# Pinduinov3-Nano-WPC-TPL521-AR.net
KiCad netlist of a schematic drawn in EAGLE
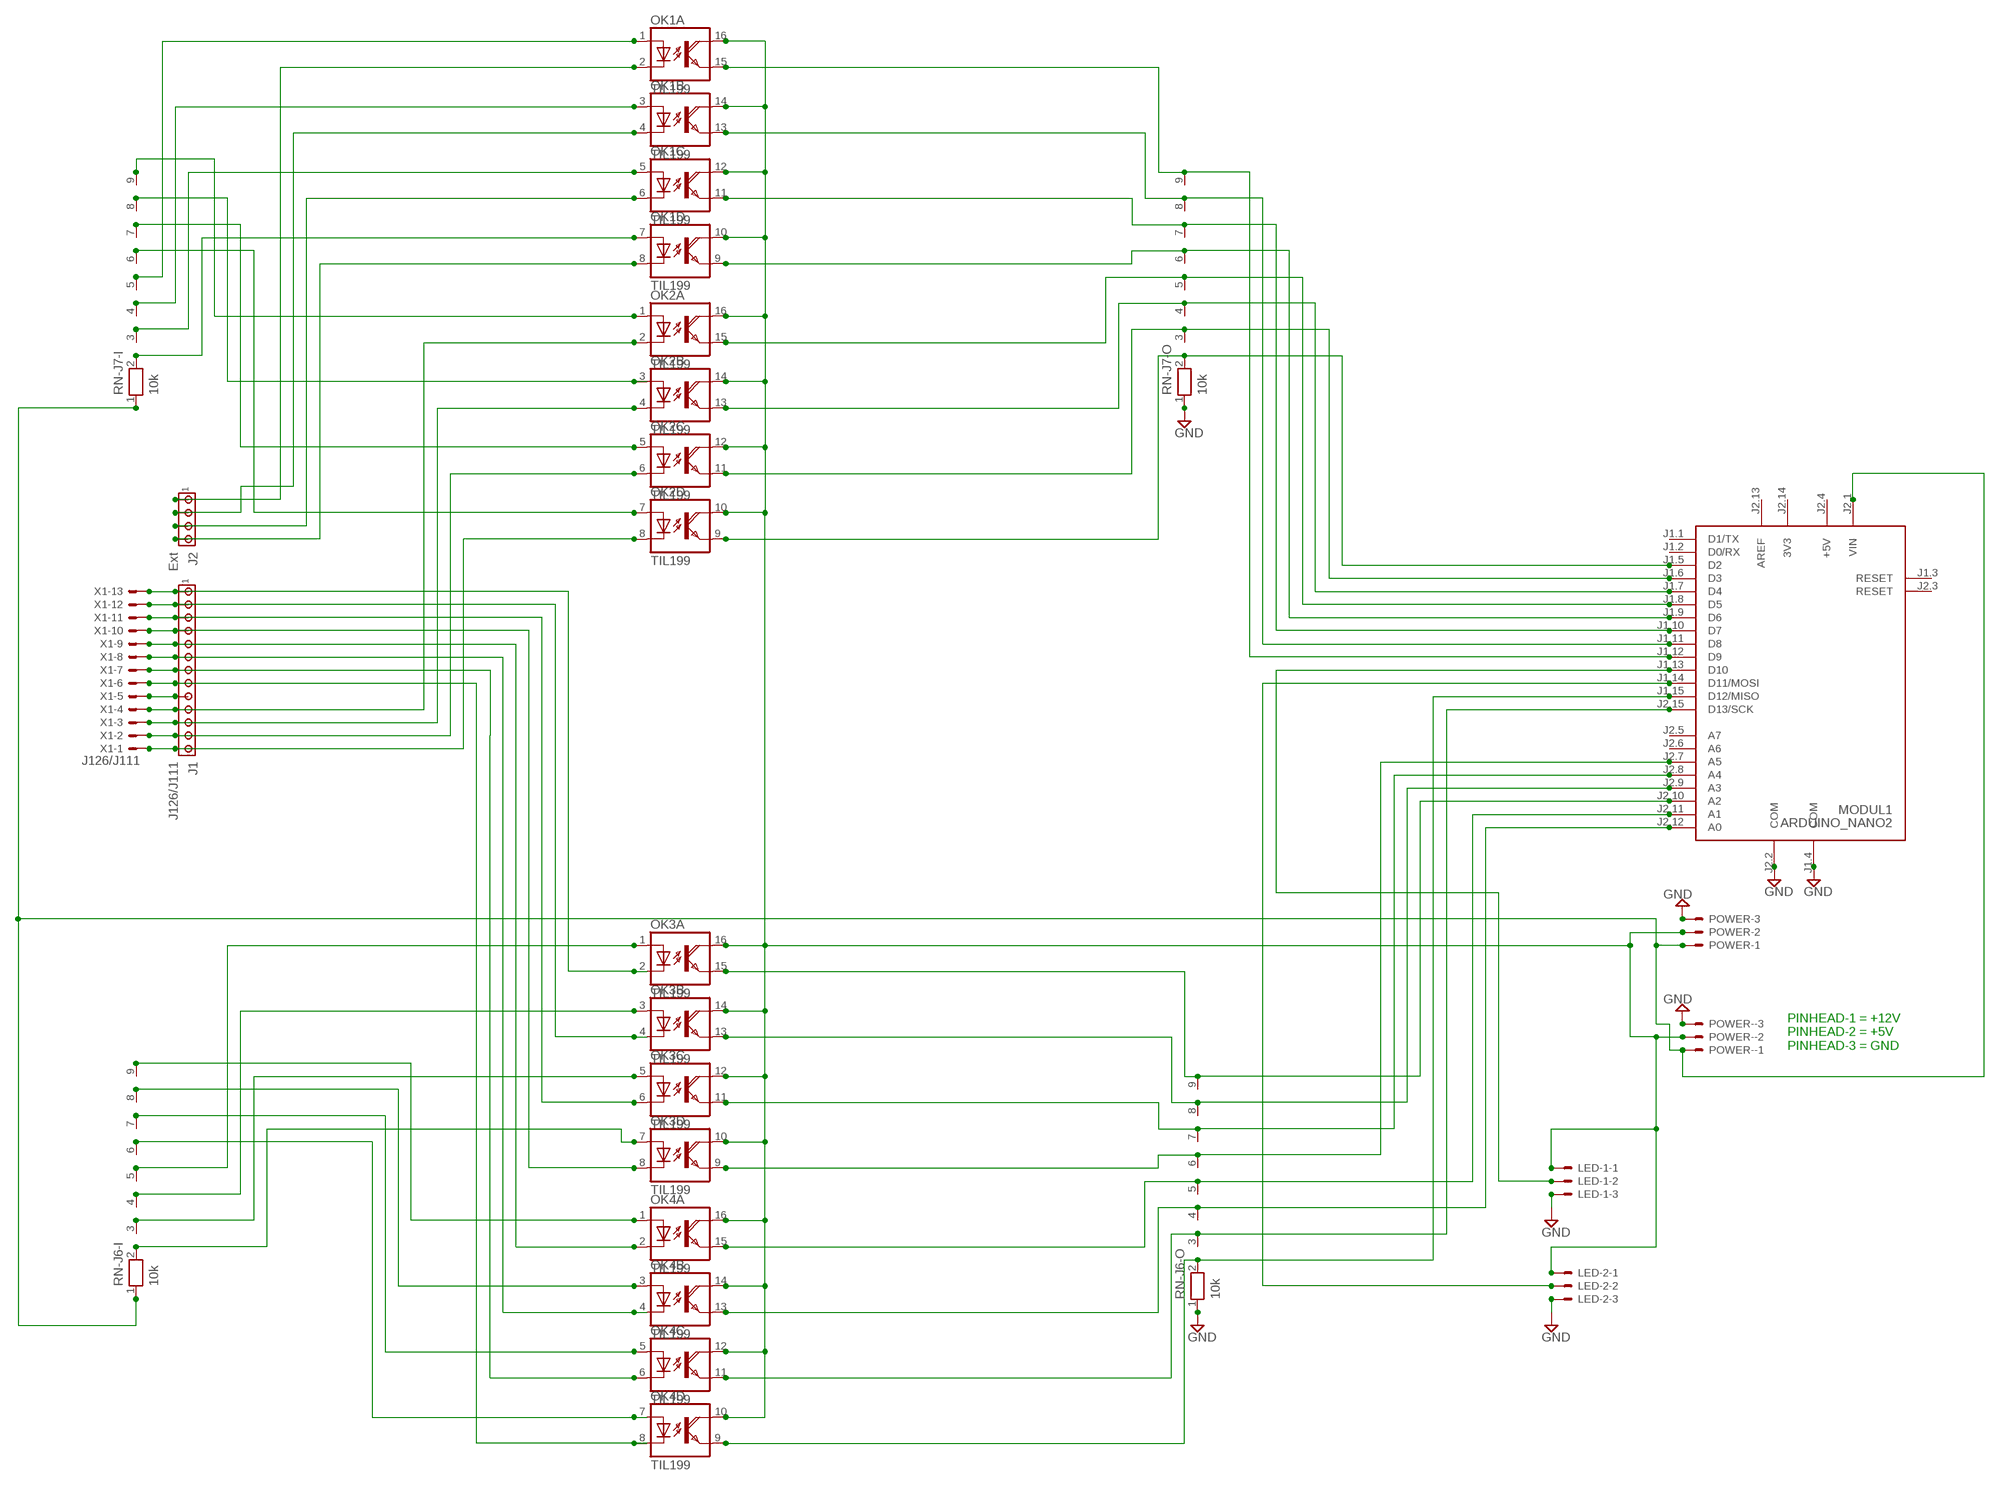
[diagram p0: schematic, sheet 1]

(export (version "E")
  (design (tool "Eeschema 10.0.6"))
  (components
    (comp (ref "J1")
      (value "J126/J111")
      (footprint "eagle-import:1X13MTA")
      (libsource (lib "eagle-import") (part "MTA13-156"))
    )
    (comp (ref "J2")
      (value "Ext")
      (footprint "eagle-import:1X4MTA")
      (libsource (lib "eagle-import") (part "MTA04-156"))
    )
    (comp (ref "LED-1")
      (value "22-23-2031")
      (footprint "eagle-import:22-23-2031")
      (fields (field (name "MF") "MOLEX"))
      (libsource (lib "eagle-import") (part "22-23-2031"))
    )
    (comp (ref "LED-2")
      (value "22-23-2031")
      (footprint "eagle-import:22-23-2031")
      (fields (field (name "MF") "MOLEX"))
      (libsource (lib "eagle-import") (part "22-23-2031"))
    )
    (comp (ref "MODUL1")
      (value "ARDUINO_NANO2")
      (footprint "eagle-import:ARDUINO_NANO2")
      (libsource (lib "eagle-import") (part "ARDUINO_NANO2"))
    )
    (comp (ref "OK1")
      (value "TIL199")
      (footprint "eagle-import:DIL16")
      (fields (field (name "MPN") "TIL 199"))
      (libsource (lib "eagle-import") (part "TIL199"))
    )
    (comp (ref "OK2")
      (value "TIL199")
      (footprint "eagle-import:DIL16")
      (fields (field (name "MPN") "TIL 199"))
      (libsource (lib "eagle-import") (part "TIL199"))
    )
    (comp (ref "OK3")
      (value "TIL199")
      (footprint "eagle-import:DIL16")
      (fields (field (name "MPN") "TIL 199"))
      (libsource (lib "eagle-import") (part "TIL199"))
    )
    (comp (ref "OK4")
      (value "TIL199")
      (footprint "eagle-import:DIL16")
      (fields (field (name "MPN") "TIL 199"))
      (libsource (lib "eagle-import") (part "TIL199"))
    )
    (comp (ref "POWER")
      (value "22-23-2031")
      (footprint "eagle-import:22-23-2031")
      (fields (field (name "MF") "MOLEX"))
      (libsource (lib "eagle-import") (part "22-23-2031"))
    )
    (comp (ref "POWER-")
      (value "22-23-2031")
      (footprint "eagle-import:22-23-2031")
      (fields (field (name "MF") "MOLEX"))
      (libsource (lib "eagle-import") (part "22-23-2031"))
    )
    (comp (ref "RN-J6-I")
      (value "10k")
      (footprint "eagle-import:RN-9")
      (libsource (lib "eagle-import") (part "RN08"))
    )
    (comp (ref "RN-J6-O")
      (value "10k")
      (footprint "eagle-import:RN-9")
      (libsource (lib "eagle-import") (part "RN08"))
    )
    (comp (ref "RN-J7-I")
      (value "10k")
      (footprint "eagle-import:RN-9")
      (libsource (lib "eagle-import") (part "RN08"))
    )
    (comp (ref "RN-J7-O")
      (value "10k")
      (footprint "eagle-import:RN-9")
      (libsource (lib "eagle-import") (part "RN08"))
    )
    (comp (ref "X1")
      (value "J126/J111")
      (footprint "eagle-import:KK-156-13")
      (libsource (lib "eagle-import") (part "KK-156-13"))
    )
  )
  (nets
    (net (code "1") (name "/+5V") (class "Default")
      (node (ref "MODUL1") (pin "J2.4") (pinfunction "+5V_J2.4") (pintype "power_in"))
    )
    (net (code "2") (name "/3V3") (class "Default")
      (node (ref "MODUL1") (pin "J2.14") (pinfunction "3V3_J2.14") (pintype "power_in"))
    )
    (net (code "3") (name "/AREF") (class "Default")
      (node (ref "MODUL1") (pin "J2.13") (pinfunction "AREF_J2.13") (pintype "power_in"))
    )
    (net (code "4") (name "GND") (class "Default")
      (node (ref "LED-1") (pin "3") (pinfunction "S_3") (pintype "passive"))
      (node (ref "LED-2") (pin "3") (pinfunction "S_3") (pintype "passive"))
      (node (ref "MODUL1") (pin "J1.4") (pinfunction "COM_J1.4") (pintype "power_in"))
      (node (ref "MODUL1") (pin "J2.2") (pinfunction "COM_J2.2") (pintype "power_in"))
      (node (ref "POWER") (pin "3") (pinfunction "S_3") (pintype "passive"))
      (node (ref "POWER-") (pin "3") (pinfunction "S_3") (pintype "passive"))
      (node (ref "RN-J6-O") (pin "1") (pinfunction "1_1") (pintype "passive"))
      (node (ref "RN-J7-O") (pin "1") (pinfunction "1_1") (pintype "passive"))
    )
    (net (code "5") (name "Net-(LED-1A-S)") (class "Default")
      (node (ref "LED-1") (pin "1") (pinfunction "S_1") (pintype "passive"))
      (node (ref "LED-2") (pin "1") (pinfunction "S_1") (pintype "passive"))
      (node (ref "OK1") (pin "10") (pinfunction "COL_10") (pintype "passive"))
      (node (ref "OK1") (pin "12") (pinfunction "COL_12") (pintype "passive"))
      (node (ref "OK1") (pin "14") (pinfunction "COL_14") (pintype "passive"))
      (node (ref "OK1") (pin "16") (pinfunction "COL_16") (pintype "passive"))
      (node (ref "OK2") (pin "10") (pinfunction "COL_10") (pintype "passive"))
      (node (ref "OK2") (pin "12") (pinfunction "COL_12") (pintype "passive"))
      (node (ref "OK2") (pin "14") (pinfunction "COL_14") (pintype "passive"))
      (node (ref "OK2") (pin "16") (pinfunction "COL_16") (pintype "passive"))
      (node (ref "OK3") (pin "10") (pinfunction "COL_10") (pintype "passive"))
      (node (ref "OK3") (pin "12") (pinfunction "COL_12") (pintype "passive"))
      (node (ref "OK3") (pin "14") (pinfunction "COL_14") (pintype "passive"))
      (node (ref "OK3") (pin "16") (pinfunction "COL_16") (pintype "passive"))
      (node (ref "OK4") (pin "10") (pinfunction "COL_10") (pintype "passive"))
      (node (ref "OK4") (pin "12") (pinfunction "COL_12") (pintype "passive"))
      (node (ref "OK4") (pin "14") (pinfunction "COL_14") (pintype "passive"))
      (node (ref "OK4") (pin "16") (pinfunction "COL_16") (pintype "passive"))
      (node (ref "POWER") (pin "2") (pinfunction "S_2") (pintype "passive"))
      (node (ref "POWER-") (pin "2") (pinfunction "S_2") (pintype "passive"))
    )
    (net (code "6") (name "Net-(LED-1B-S)") (class "Default")
      (node (ref "LED-1") (pin "2") (pinfunction "S_2") (pintype "passive"))
      (node (ref "MODUL1") (pin "J1.13") (pinfunction "D10_J1.13") (pintype "bidirectional"))
    )
    (net (code "7") (name "Net-(LED-2B-S)") (class "Default")
      (node (ref "LED-2") (pin "2") (pinfunction "S_2") (pintype "passive"))
      (node (ref "MODUL1") (pin "J1.14") (pinfunction "D11/MOSI_J1.14") (pintype "bidirectional"))
    )
    (net (code "8") (name "Net-(MODUL1-A0)") (class "Default")
      (node (ref "MODUL1") (pin "J2.12") (pinfunction "A0_J2.12") (pintype "bidirectional"))
      (node (ref "OK4") (pin "13") (pinfunction "EMI_13") (pintype "passive"))
      (node (ref "RN-J6-O") (pin "4") (pinfunction "4_4") (pintype "passive"))
    )
    (net (code "9") (name "Net-(MODUL1-A1)") (class "Default")
      (node (ref "MODUL1") (pin "J2.11") (pinfunction "A1_J2.11") (pintype "bidirectional"))
      (node (ref "OK4") (pin "15") (pinfunction "EMI_15") (pintype "passive"))
      (node (ref "RN-J6-O") (pin "5") (pinfunction "5_5") (pintype "passive"))
    )
    (net (code "10") (name "Net-(MODUL1-A2)") (class "Default")
      (node (ref "MODUL1") (pin "J2.10") (pinfunction "A2_J2.10") (pintype "bidirectional"))
      (node (ref "OK3") (pin "15") (pinfunction "EMI_15") (pintype "passive"))
      (node (ref "RN-J6-O") (pin "9") (pinfunction "9_9") (pintype "passive"))
    )
    (net (code "11") (name "Net-(MODUL1-A3)") (class "Default")
      (node (ref "MODUL1") (pin "J2.9") (pinfunction "A3_J2.9") (pintype "bidirectional"))
      (node (ref "OK3") (pin "13") (pinfunction "EMI_13") (pintype "passive"))
      (node (ref "RN-J6-O") (pin "8") (pinfunction "8_8") (pintype "passive"))
    )
    (net (code "12") (name "Net-(MODUL1-A4)") (class "Default")
      (node (ref "MODUL1") (pin "J2.8") (pinfunction "A4_J2.8") (pintype "bidirectional"))
      (node (ref "OK3") (pin "11") (pinfunction "EMI_11") (pintype "passive"))
      (node (ref "RN-J6-O") (pin "7") (pinfunction "7_7") (pintype "passive"))
    )
    (net (code "13") (name "Net-(MODUL1-A5)") (class "Default")
      (node (ref "MODUL1") (pin "J2.7") (pinfunction "A5_J2.7") (pintype "bidirectional"))
      (node (ref "OK3") (pin "9") (pinfunction "EMI_9") (pintype "passive"))
      (node (ref "RN-J6-O") (pin "6") (pinfunction "6_6") (pintype "passive"))
    )
    (net (code "14") (name "Net-(MODUL1-D2)") (class "Default")
      (node (ref "MODUL1") (pin "J1.5") (pinfunction "D2_J1.5") (pintype "bidirectional"))
      (node (ref "OK2") (pin "9") (pinfunction "EMI_9") (pintype "passive"))
      (node (ref "RN-J7-O") (pin "2") (pinfunction "2_2") (pintype "passive"))
    )
    (net (code "15") (name "Net-(MODUL1-D3)") (class "Default")
      (node (ref "MODUL1") (pin "J1.6") (pinfunction "D3_J1.6") (pintype "bidirectional"))
      (node (ref "OK2") (pin "11") (pinfunction "EMI_11") (pintype "passive"))
      (node (ref "RN-J7-O") (pin "3") (pinfunction "3_3") (pintype "passive"))
    )
    (net (code "16") (name "Net-(MODUL1-D4)") (class "Default")
      (node (ref "MODUL1") (pin "J1.7") (pinfunction "D4_J1.7") (pintype "bidirectional"))
      (node (ref "OK2") (pin "13") (pinfunction "EMI_13") (pintype "passive"))
      (node (ref "RN-J7-O") (pin "4") (pinfunction "4_4") (pintype "passive"))
    )
    (net (code "17") (name "Net-(MODUL1-D5)") (class "Default")
      (node (ref "MODUL1") (pin "J1.8") (pinfunction "D5_J1.8") (pintype "bidirectional"))
      (node (ref "OK2") (pin "15") (pinfunction "EMI_15") (pintype "passive"))
      (node (ref "RN-J7-O") (pin "5") (pinfunction "5_5") (pintype "passive"))
    )
    (net (code "18") (name "Net-(MODUL1-D6)") (class "Default")
      (node (ref "MODUL1") (pin "J1.9") (pinfunction "D6_J1.9") (pintype "bidirectional"))
      (node (ref "OK1") (pin "9") (pinfunction "EMI_9") (pintype "passive"))
      (node (ref "RN-J7-O") (pin "6") (pinfunction "6_6") (pintype "passive"))
    )
    (net (code "19") (name "Net-(MODUL1-D7)") (class "Default")
      (node (ref "MODUL1") (pin "J1.10") (pinfunction "D7_J1.10") (pintype "bidirectional"))
      (node (ref "OK1") (pin "11") (pinfunction "EMI_11") (pintype "passive"))
      (node (ref "RN-J7-O") (pin "7") (pinfunction "7_7") (pintype "passive"))
    )
    (net (code "20") (name "Net-(MODUL1-D8)") (class "Default")
      (node (ref "MODUL1") (pin "J1.11") (pinfunction "D8_J1.11") (pintype "bidirectional"))
      (node (ref "OK1") (pin "13") (pinfunction "EMI_13") (pintype "passive"))
      (node (ref "RN-J7-O") (pin "8") (pinfunction "8_8") (pintype "passive"))
    )
    (net (code "21") (name "Net-(MODUL1-D9)") (class "Default")
      (node (ref "MODUL1") (pin "J1.12") (pinfunction "D9_J1.12") (pintype "bidirectional"))
      (node (ref "OK1") (pin "15") (pinfunction "EMI_15") (pintype "passive"))
      (node (ref "RN-J7-O") (pin "9") (pinfunction "9_9") (pintype "passive"))
    )
    (net (code "22") (name "Net-(MODUL1-D12{slash}MISO)") (class "Default")
      (node (ref "MODUL1") (pin "J1.15") (pinfunction "D12/MISO_J1.15") (pintype "bidirectional"))
      (node (ref "OK4") (pin "9") (pinfunction "EMI_9") (pintype "passive"))
      (node (ref "RN-J6-O") (pin "2") (pinfunction "2_2") (pintype "passive"))
    )
    (net (code "23") (name "Net-(MODUL1-D13{slash}SCK)") (class "Default")
      (node (ref "MODUL1") (pin "J2.15") (pinfunction "D13/SCK_J2.15") (pintype "bidirectional"))
      (node (ref "OK4") (pin "11") (pinfunction "EMI_11") (pintype "passive"))
      (node (ref "RN-J6-O") (pin "3") (pinfunction "3_3") (pintype "passive"))
    )
    (net (code "24") (name "Net-(MODUL1-VIN)") (class "Default")
      (node (ref "MODUL1") (pin "J2.1") (pinfunction "VIN_J2.1") (pintype "power_in"))
      (node (ref "POWER") (pin "1") (pinfunction "S_1") (pintype "passive"))
      (node (ref "POWER-") (pin "1") (pinfunction "S_1") (pintype "passive"))
      (node (ref "RN-J6-I") (pin "1") (pinfunction "1_1") (pintype "passive"))
      (node (ref "RN-J7-I") (pin "1") (pinfunction "1_1") (pintype "passive"))
    )
    (net (code "25") (name "Net-(OK1A-A)") (class "Default")
      (node (ref "OK1") (pin "1") (pinfunction "A_1") (pintype "passive"))
      (node (ref "RN-J7-I") (pin "5") (pinfunction "5_5") (pintype "passive"))
    )
    (net (code "26") (name "Net-(OK1A-C)") (class "Default")
      (node (ref "J2") (pin "1") (pinfunction "1_1") (pintype "passive"))
      (node (ref "OK1") (pin "2") (pinfunction "C_2") (pintype "passive"))
    )
    (net (code "27") (name "Net-(OK1B-A)") (class "Default")
      (node (ref "OK1") (pin "3") (pinfunction "A_3") (pintype "passive"))
      (node (ref "RN-J7-I") (pin "4") (pinfunction "4_4") (pintype "passive"))
    )
    (net (code "28") (name "Net-(OK1B-C)") (class "Default")
      (node (ref "J2") (pin "2") (pinfunction "2_2") (pintype "passive"))
      (node (ref "OK1") (pin "4") (pinfunction "C_4") (pintype "passive"))
    )
    (net (code "29") (name "Net-(OK1C-A)") (class "Default")
      (node (ref "OK1") (pin "5") (pinfunction "A_5") (pintype "passive"))
      (node (ref "RN-J7-I") (pin "3") (pinfunction "3_3") (pintype "passive"))
    )
    (net (code "30") (name "Net-(OK1C-C)") (class "Default")
      (node (ref "J2") (pin "3") (pinfunction "3_3") (pintype "passive"))
      (node (ref "OK1") (pin "6") (pinfunction "C_6") (pintype "passive"))
    )
    (net (code "31") (name "Net-(OK1D-A)") (class "Default")
      (node (ref "OK1") (pin "7") (pinfunction "A_7") (pintype "passive"))
      (node (ref "RN-J7-I") (pin "2") (pinfunction "2_2") (pintype "passive"))
    )
    (net (code "32") (name "Net-(OK1D-C)") (class "Default")
      (node (ref "J2") (pin "4") (pinfunction "4_4") (pintype "passive"))
      (node (ref "OK1") (pin "8") (pinfunction "C_8") (pintype "passive"))
    )
    (net (code "33") (name "Net-(OK2A-A)") (class "Default")
      (node (ref "OK2") (pin "1") (pinfunction "A_1") (pintype "passive"))
      (node (ref "RN-J7-I") (pin "9") (pinfunction "9_9") (pintype "passive"))
    )
    (net (code "34") (name "Net-(OK2A-C)") (class "Default")
      (node (ref "J1") (pin "10") (pinfunction "10_10") (pintype "passive"))
      (node (ref "OK2") (pin "2") (pinfunction "C_2") (pintype "passive"))
      (node (ref "X1") (pin "4") (pinfunction "S_4") (pintype "passive"))
    )
    (net (code "35") (name "Net-(OK2B-A)") (class "Default")
      (node (ref "OK2") (pin "3") (pinfunction "A_3") (pintype "passive"))
      (node (ref "RN-J7-I") (pin "8") (pinfunction "8_8") (pintype "passive"))
    )
    (net (code "36") (name "Net-(OK2B-C)") (class "Default")
      (node (ref "J1") (pin "11") (pinfunction "11_11") (pintype "passive"))
      (node (ref "OK2") (pin "4") (pinfunction "C_4") (pintype "passive"))
      (node (ref "X1") (pin "3") (pinfunction "S_3") (pintype "passive"))
    )
    (net (code "37") (name "Net-(OK2C-A)") (class "Default")
      (node (ref "OK2") (pin "5") (pinfunction "A_5") (pintype "passive"))
      (node (ref "RN-J7-I") (pin "7") (pinfunction "7_7") (pintype "passive"))
    )
    (net (code "38") (name "Net-(OK2C-C)") (class "Default")
      (node (ref "J1") (pin "12") (pinfunction "12_12") (pintype "passive"))
      (node (ref "OK2") (pin "6") (pinfunction "C_6") (pintype "passive"))
      (node (ref "X1") (pin "2") (pinfunction "S_2") (pintype "passive"))
    )
    (net (code "39") (name "Net-(OK2D-A)") (class "Default")
      (node (ref "OK2") (pin "7") (pinfunction "A_7") (pintype "passive"))
      (node (ref "RN-J7-I") (pin "6") (pinfunction "6_6") (pintype "passive"))
    )
    (net (code "40") (name "Net-(OK2D-C)") (class "Default")
      (node (ref "J1") (pin "13") (pinfunction "13_13") (pintype "passive"))
      (node (ref "OK2") (pin "8") (pinfunction "C_8") (pintype "passive"))
      (node (ref "X1") (pin "1") (pinfunction "S_1") (pintype "passive"))
    )
    (net (code "41") (name "Net-(OK3A-A)") (class "Default")
      (node (ref "OK3") (pin "1") (pinfunction "A_1") (pintype "passive"))
      (node (ref "RN-J6-I") (pin "5") (pinfunction "5_5") (pintype "passive"))
    )
    (net (code "42") (name "Net-(OK3A-C)") (class "Default")
      (node (ref "J1") (pin "1") (pinfunction "1_1") (pintype "passive"))
      (node (ref "OK3") (pin "2") (pinfunction "C_2") (pintype "passive"))
      (node (ref "X1") (pin "13") (pinfunction "S_13") (pintype "passive"))
    )
    (net (code "43") (name "Net-(OK3B-A)") (class "Default")
      (node (ref "OK3") (pin "3") (pinfunction "A_3") (pintype "passive"))
      (node (ref "RN-J6-I") (pin "4") (pinfunction "4_4") (pintype "passive"))
    )
    (net (code "44") (name "Net-(OK3B-C)") (class "Default")
      (node (ref "J1") (pin "2") (pinfunction "2_2") (pintype "passive"))
      (node (ref "OK3") (pin "4") (pinfunction "C_4") (pintype "passive"))
      (node (ref "X1") (pin "12") (pinfunction "S_12") (pintype "passive"))
    )
    (net (code "45") (name "Net-(OK3C-A)") (class "Default")
      (node (ref "OK3") (pin "5") (pinfunction "A_5") (pintype "passive"))
      (node (ref "RN-J6-I") (pin "3") (pinfunction "3_3") (pintype "passive"))
    )
    (net (code "46") (name "Net-(OK3C-C)") (class "Default")
      (node (ref "J1") (pin "3") (pinfunction "3_3") (pintype "passive"))
      (node (ref "OK3") (pin "6") (pinfunction "C_6") (pintype "passive"))
      (node (ref "X1") (pin "11") (pinfunction "S_11") (pintype "passive"))
    )
    (net (code "47") (name "Net-(OK3D-A)") (class "Default")
      (node (ref "OK3") (pin "7") (pinfunction "A_7") (pintype "passive"))
      (node (ref "RN-J6-I") (pin "2") (pinfunction "2_2") (pintype "passive"))
    )
    (net (code "48") (name "Net-(OK3D-C)") (class "Default")
      (node (ref "J1") (pin "4") (pinfunction "4_4") (pintype "passive"))
      (node (ref "OK3") (pin "8") (pinfunction "C_8") (pintype "passive"))
      (node (ref "X1") (pin "10") (pinfunction "S_10") (pintype "passive"))
    )
    (net (code "49") (name "Net-(OK4A-A)") (class "Default")
      (node (ref "OK4") (pin "1") (pinfunction "A_1") (pintype "passive"))
      (node (ref "RN-J6-I") (pin "9") (pinfunction "9_9") (pintype "passive"))
    )
    (net (code "50") (name "Net-(OK4A-C)") (class "Default")
      (node (ref "J1") (pin "5") (pinfunction "5_5") (pintype "passive"))
      (node (ref "OK4") (pin "2") (pinfunction "C_2") (pintype "passive"))
      (node (ref "X1") (pin "9") (pinfunction "S_9") (pintype "passive"))
    )
    (net (code "51") (name "Net-(OK4B-A)") (class "Default")
      (node (ref "OK4") (pin "3") (pinfunction "A_3") (pintype "passive"))
      (node (ref "RN-J6-I") (pin "8") (pinfunction "8_8") (pintype "passive"))
    )
    (net (code "52") (name "Net-(OK4B-C)") (class "Default")
      (node (ref "J1") (pin "6") (pinfunction "6_6") (pintype "passive"))
      (node (ref "OK4") (pin "4") (pinfunction "C_4") (pintype "passive"))
      (node (ref "X1") (pin "8") (pinfunction "S_8") (pintype "passive"))
    )
    (net (code "53") (name "Net-(OK4C-A)") (class "Default")
      (node (ref "OK4") (pin "5") (pinfunction "A_5") (pintype "passive"))
      (node (ref "RN-J6-I") (pin "7") (pinfunction "7_7") (pintype "passive"))
    )
    (net (code "54") (name "Net-(OK4C-C)") (class "Default")
      (node (ref "J1") (pin "7") (pinfunction "7_7") (pintype "passive"))
      (node (ref "OK4") (pin "6") (pinfunction "C_6") (pintype "passive"))
      (node (ref "X1") (pin "7") (pinfunction "S_7") (pintype "passive"))
    )
    (net (code "55") (name "Net-(OK4D-A)") (class "Default")
      (node (ref "OK4") (pin "7") (pinfunction "A_7") (pintype "passive"))
      (node (ref "RN-J6-I") (pin "6") (pinfunction "6_6") (pintype "passive"))
    )
    (net (code "56") (name "Net-(OK4D-C)") (class "Default")
      (node (ref "J1") (pin "8") (pinfunction "8_8") (pintype "passive"))
      (node (ref "OK4") (pin "8") (pinfunction "C_8") (pintype "passive"))
      (node (ref "X1") (pin "6") (pinfunction "S_6") (pintype "passive"))
    )
    (net (code "57") (name "Net-(X1I-S)") (class "Default")
      (node (ref "J1") (pin "9") (pinfunction "9_9") (pintype "passive"))
      (node (ref "X1") (pin "5") (pinfunction "S_5") (pintype "passive"))
    )
    (net (code "58") (name "unconnected-(MODUL1-A6-PadJ2.6)") (class "Default")
      (node (ref "MODUL1") (pin "J2.6") (pinfunction "A6_J2.6") (pintype "bidirectional"))
    )
    (net (code "59") (name "unconnected-(MODUL1-A7-PadJ2.5)") (class "Default")
      (node (ref "MODUL1") (pin "J2.5") (pinfunction "A7_J2.5") (pintype "bidirectional"))
    )
    (net (code "60") (name "unconnected-(MODUL1-D0{slash}RX-PadJ1.2)") (class "Default")
      (node (ref "MODUL1") (pin "J1.2") (pinfunction "D0/RX_J1.2") (pintype "bidirectional"))
    )
    (net (code "61") (name "unconnected-(MODUL1-D1{slash}TX-PadJ1.1)") (class "Default")
      (node (ref "MODUL1") (pin "J1.1") (pinfunction "D1/TX_J1.1") (pintype "bidirectional"))
    )
    (net (code "62") (name "unconnected-(MODUL1-RESET-PadJ1.3)") (class "Default")
      (node (ref "MODUL1") (pin "J1.3") (pinfunction "RESET_J1.3") (pintype "bidirectional"))
    )
    (net (code "63") (name "unconnected-(MODUL1-RESET-PadJ2.3)") (class "Default")
      (node (ref "MODUL1") (pin "J2.3") (pinfunction "RESET_J2.3") (pintype "bidirectional"))
    )
  )
)
